# main.net
KiCad netlist of a schematic drawn in EAGLE
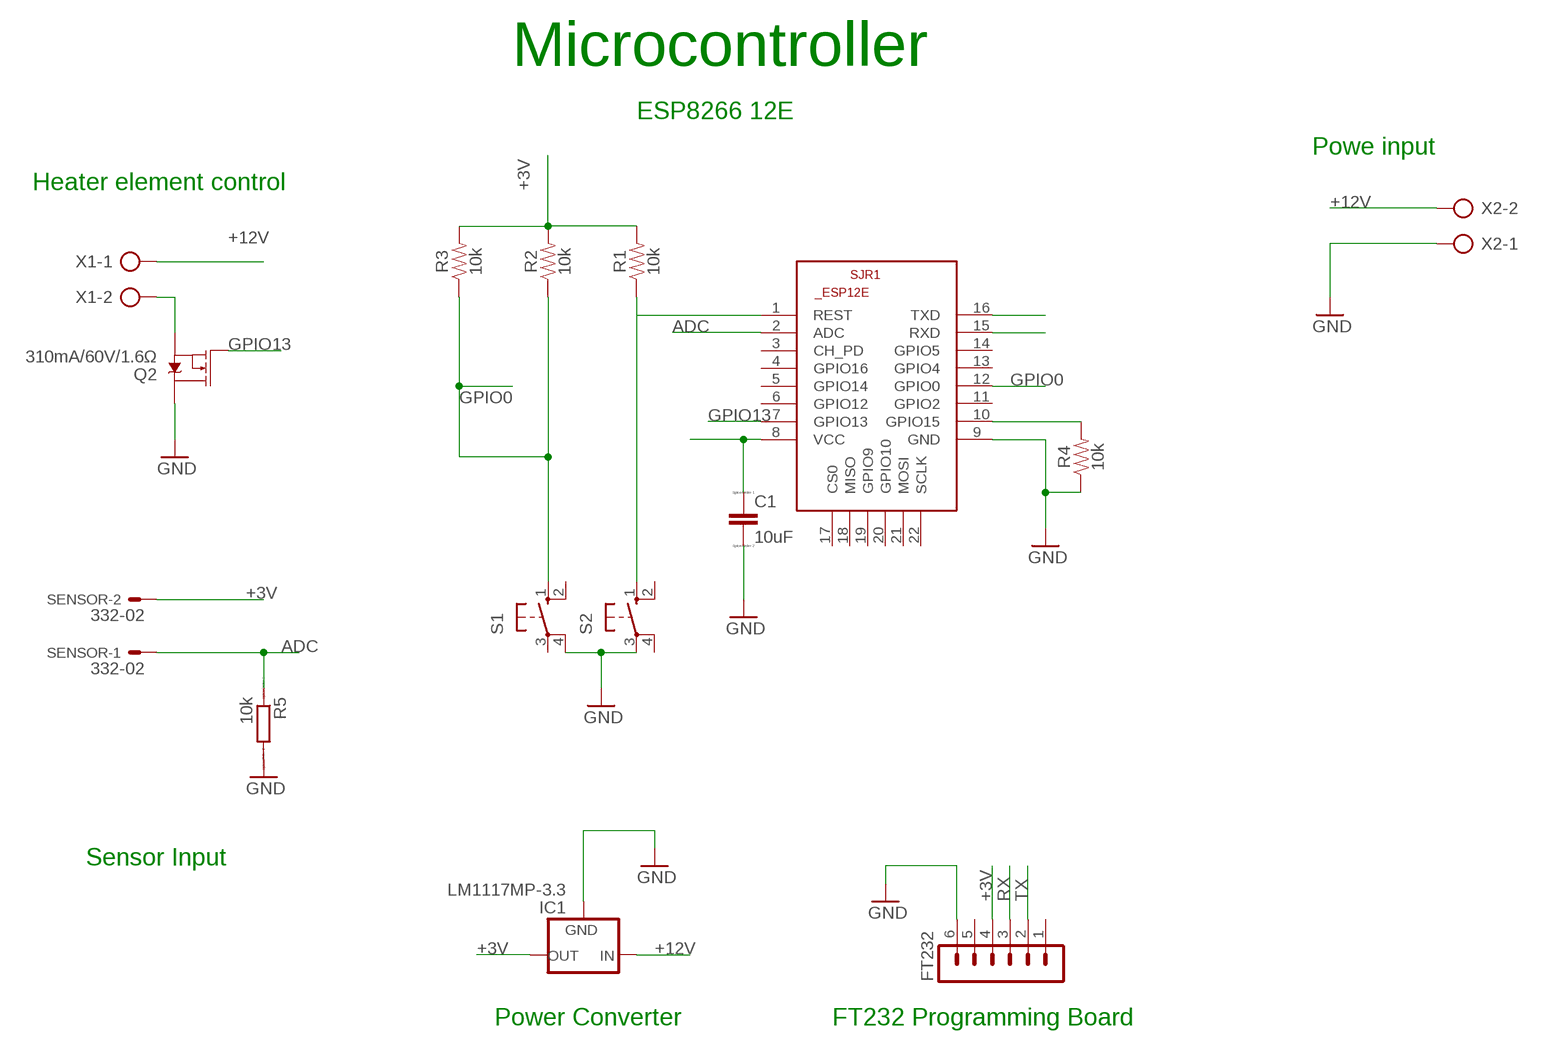
[diagram p0: schematic, sheet 1]

(export (version "E")
  (design (tool "Eeschema 10.0.6"))
  (components
    (comp (ref "C1")
      (value "10uF")
      (footprint "eagle-import:C1206")
      (libsource (lib "eagle-import") (part "CC1206"))
    )
    (comp (ref "FT232")
      (value "MA06-1")
      (footprint "eagle-import:MA06-1")
      (libsource (lib "eagle-import") (part "MA06-1"))
    )
    (comp (ref "IC1")
      (value "LM1117MP-3.3")
      (footprint "eagle-import:SOT223")
      (fields (field (name "MF") "Texas Instruments"))
      (libsource (lib "eagle-import") (part "LM1117?-MP3.3"))
    )
    (comp (ref "Q2")
      (value "310mA/60V/1.6Ω")
      (footprint "eagle-import:SOT323")
      (libsource (lib "eagle-import") (part "MOSFET-NCH-2N7002PW"))
    )
    (comp (ref "R1")
      (value "10k")
      (footprint "eagle-import:0603")
      (libsource (lib "eagle-import") (part "10KOHM-0603-1/10W-1%"))
    )
    (comp (ref "R2")
      (value "10k")
      (footprint "eagle-import:0603")
      (libsource (lib "eagle-import") (part "10KOHM-0603-1/10W-1%"))
    )
    (comp (ref "R3")
      (value "10k")
      (footprint "eagle-import:0603")
      (libsource (lib "eagle-import") (part "10KOHM-0603-1/10W-1%"))
    )
    (comp (ref "R4")
      (value "10k")
      (footprint "eagle-import:0603")
      (libsource (lib "eagle-import") (part "10KOHM-0603-1/10W-1%"))
    )
    (comp (ref "R5")
      (value "10k")
      (footprint "eagle-import:R1206")
      (libsource (lib "eagle-import") (part "RR1206"))
    )
    (comp (ref "S1")
      (value "10-XX")
      (footprint "eagle-import:B3F-10XX")
      (fields (field (name "MPN") "B3F-1000"))
      (libsource (lib "eagle-import") (part "10-XX"))
    )
    (comp (ref "S2")
      (value "10-XX")
      (footprint "eagle-import:B3F-10XX")
      (fields (field (name "MPN") "B3F-1000"))
      (libsource (lib "eagle-import") (part "10-XX"))
    )
    (comp (ref "SENSOR")
      (value "332-02")
      (footprint "eagle-import:332-02")
      (libsource (lib "eagle-import") (part "332-02"))
    )
    (comp (ref "SJR1")
      (value "ESP8266-12EESP12E")
      (footprint "eagle-import:ESP8266-ESP12E")
      (libsource (lib "eagle-import") (part "ESP8266-12EESP12E"))
    )
    (comp (ref "X1")
      (value "AK500/2")
      (footprint "eagle-import:AK500_2")
      (libsource (lib "eagle-import") (part "AK500/2"))
    )
    (comp (ref "X2")
      (value "AK500/2")
      (footprint "eagle-import:AK500_2")
      (libsource (lib "eagle-import") (part "AK500/2"))
    )
  )
  (nets
    (net (code "1") (name "/+3V") (class "Default")
      (node (ref "C1") (pin "1") (pinfunction "1_1") (pintype "passive"))
      (node (ref "FT232") (pin "4") (pinfunction "4_4") (pintype "passive"))
      (node (ref "IC1") (pin "2") (pinfunction "OUT_2") (pintype "passive"))
      (node (ref "IC1") (pin "4") (pinfunction "OUT_4") (pintype "passive"))
      (node (ref "R1") (pin "2") (pinfunction "2_2") (pintype "passive"))
      (node (ref "R2") (pin "2") (pinfunction "2_2") (pintype "passive"))
      (node (ref "R3") (pin "2") (pinfunction "2_2") (pintype "passive"))
      (node (ref "SENSOR") (pin "2") (pinfunction "S_2") (pintype "passive"))
      (node (ref "SJR1") (pin "8") (pinfunction "VCC_8") (pintype "bidirectional"))
    )
    (net (code "2") (name "/+12V") (class "Default")
      (node (ref "IC1") (pin "3") (pinfunction "IN_3") (pintype "input"))
      (node (ref "X1") (pin "1") (pinfunction "KL_1") (pintype "passive"))
      (node (ref "X2") (pin "2") (pinfunction "KL_2") (pintype "passive"))
    )
    (net (code "3") (name "/ADC") (class "Default")
      (node (ref "R5") (pin "1") (pinfunction "1_1") (pintype "passive"))
      (node (ref "SENSOR") (pin "1") (pinfunction "S_1") (pintype "passive"))
      (node (ref "SJR1") (pin "2") (pinfunction "ADC_2") (pintype "bidirectional"))
    )
    (net (code "4") (name "/GPIO0") (class "Default")
      (node (ref "R2") (pin "1") (pinfunction "1_1") (pintype "passive"))
      (node (ref "R3") (pin "1") (pinfunction "1_1") (pintype "passive"))
      (node (ref "S1") (pin "1") (pinfunction "S_1") (pintype "passive"))
      (node (ref "SJR1") (pin "12") (pinfunction "GPIO0_12") (pintype "bidirectional"))
    )
    (net (code "5") (name "/GPIO13") (class "Default")
      (node (ref "Q2") (pin "1") (pinfunction "G_1") (pintype "bidirectional"))
      (node (ref "SJR1") (pin "7") (pinfunction "GPIO13_7") (pintype "bidirectional"))
    )
    (net (code "6") (name "/RX") (class "Default")
      (node (ref "FT232") (pin "3") (pinfunction "3_3") (pintype "passive"))
      (node (ref "SJR1") (pin "15") (pinfunction "RXD_15") (pintype "bidirectional"))
    )
    (net (code "7") (name "/TX") (class "Default")
      (node (ref "FT232") (pin "2") (pinfunction "2_2") (pintype "passive"))
      (node (ref "SJR1") (pin "16") (pinfunction "TXD_16") (pintype "bidirectional"))
    )
    (net (code "8") (name "GND") (class "Default")
      (node (ref "C1") (pin "2") (pinfunction "2_2") (pintype "passive"))
      (node (ref "FT232") (pin "6") (pinfunction "6_6") (pintype "passive"))
      (node (ref "IC1") (pin "1") (pinfunction "GND_1") (pintype "input"))
      (node (ref "Q2") (pin "3") (pinfunction "D_3") (pintype "bidirectional"))
      (node (ref "R4") (pin "1") (pinfunction "1_1") (pintype "passive"))
      (node (ref "R5") (pin "2") (pinfunction "2_2") (pintype "passive"))
      (node (ref "S1") (pin "4") (pinfunction "P1_4") (pintype "passive"))
      (node (ref "S2") (pin "3") (pinfunction "P_3") (pintype "passive"))
      (node (ref "SJR1") (pin "9") (pinfunction "GND_9") (pintype "bidirectional"))
      (node (ref "X2") (pin "1") (pinfunction "KL_1") (pintype "passive"))
    )
    (net (code "9") (name "Net-(Q2-S)") (class "Default")
      (node (ref "Q2") (pin "2") (pinfunction "S_2") (pintype "bidirectional"))
      (node (ref "X1") (pin "2") (pinfunction "KL_2") (pintype "passive"))
    )
    (net (code "10") (name "Net-(S2-S)") (class "Default")
      (node (ref "R1") (pin "1") (pinfunction "1_1") (pintype "passive"))
      (node (ref "S2") (pin "1") (pinfunction "S_1") (pintype "passive"))
      (node (ref "SJR1") (pin "1") (pinfunction "REST_1") (pintype "bidirectional"))
    )
    (net (code "11") (name "Net-(SJR1-GPIO15)") (class "Default")
      (node (ref "R4") (pin "2") (pinfunction "2_2") (pintype "passive"))
      (node (ref "SJR1") (pin "10") (pinfunction "GPIO15_10") (pintype "bidirectional"))
    )
    (net (code "12") (name "unconnected-(FT232-Pad1)") (class "Default")
      (node (ref "FT232") (pin "1") (pinfunction "1_1") (pintype "passive"))
    )
    (net (code "13") (name "unconnected-(FT232-Pad5)") (class "Default")
      (node (ref "FT232") (pin "5") (pinfunction "5_5") (pintype "passive"))
    )
    (net (code "14") (name "unconnected-(S1-P-Pad3)") (class "Default")
      (node (ref "S1") (pin "3") (pinfunction "P_3") (pintype "passive"))
    )
    (net (code "15") (name "unconnected-(S1-S1-Pad2)") (class "Default")
      (node (ref "S1") (pin "2") (pinfunction "S1_2") (pintype "passive"))
    )
    (net (code "16") (name "unconnected-(S2-P1-Pad4)") (class "Default")
      (node (ref "S2") (pin "4") (pinfunction "P1_4") (pintype "passive"))
    )
    (net (code "17") (name "unconnected-(S2-S1-Pad2)") (class "Default")
      (node (ref "S2") (pin "2") (pinfunction "S1_2") (pintype "passive"))
    )
    (net (code "18") (name "unconnected-(SJR1-CH_PD-Pad3)") (class "Default")
      (node (ref "SJR1") (pin "3") (pinfunction "CH_PD_3") (pintype "bidirectional"))
    )
    (net (code "19") (name "unconnected-(SJR1-CS0-Pad17)") (class "Default")
      (node (ref "SJR1") (pin "17") (pinfunction "CS0_17") (pintype "bidirectional"))
    )
    (net (code "20") (name "unconnected-(SJR1-GPIO2-Pad11)") (class "Default")
      (node (ref "SJR1") (pin "11") (pinfunction "GPIO2_11") (pintype "bidirectional"))
    )
    (net (code "21") (name "unconnected-(SJR1-GPIO4-Pad13)") (class "Default")
      (node (ref "SJR1") (pin "13") (pinfunction "GPIO4_13") (pintype "bidirectional"))
    )
    (net (code "22") (name "unconnected-(SJR1-GPIO5-Pad14)") (class "Default")
      (node (ref "SJR1") (pin "14") (pinfunction "GPIO5_14") (pintype "bidirectional"))
    )
    (net (code "23") (name "unconnected-(SJR1-GPIO9-Pad19)") (class "Default")
      (node (ref "SJR1") (pin "19") (pinfunction "GPIO9_19") (pintype "bidirectional"))
    )
    (net (code "24") (name "unconnected-(SJR1-GPIO10-Pad20)") (class "Default")
      (node (ref "SJR1") (pin "20") (pinfunction "GPIO10_20") (pintype "bidirectional"))
    )
    (net (code "25") (name "unconnected-(SJR1-GPIO12-Pad6)") (class "Default")
      (node (ref "SJR1") (pin "6") (pinfunction "GPIO12_6") (pintype "bidirectional"))
    )
    (net (code "26") (name "unconnected-(SJR1-GPIO14-Pad5)") (class "Default")
      (node (ref "SJR1") (pin "5") (pinfunction "GPIO14_5") (pintype "bidirectional"))
    )
    (net (code "27") (name "unconnected-(SJR1-GPIO16-Pad4)") (class "Default")
      (node (ref "SJR1") (pin "4") (pinfunction "GPIO16_4") (pintype "bidirectional"))
    )
    (net (code "28") (name "unconnected-(SJR1-MISO-Pad18)") (class "Default")
      (node (ref "SJR1") (pin "18") (pinfunction "MISO_18") (pintype "bidirectional"))
    )
    (net (code "29") (name "unconnected-(SJR1-MOSI-Pad21)") (class "Default")
      (node (ref "SJR1") (pin "21") (pinfunction "MOSI_21") (pintype "bidirectional"))
    )
    (net (code "30") (name "unconnected-(SJR1-SCLK-Pad22)") (class "Default")
      (node (ref "SJR1") (pin "22") (pinfunction "SCLK_22") (pintype "bidirectional"))
    )
  )
)
